# 1-Schematic_ceiling-light.net
KiCad netlist of a schematic drawn in EasyEDA
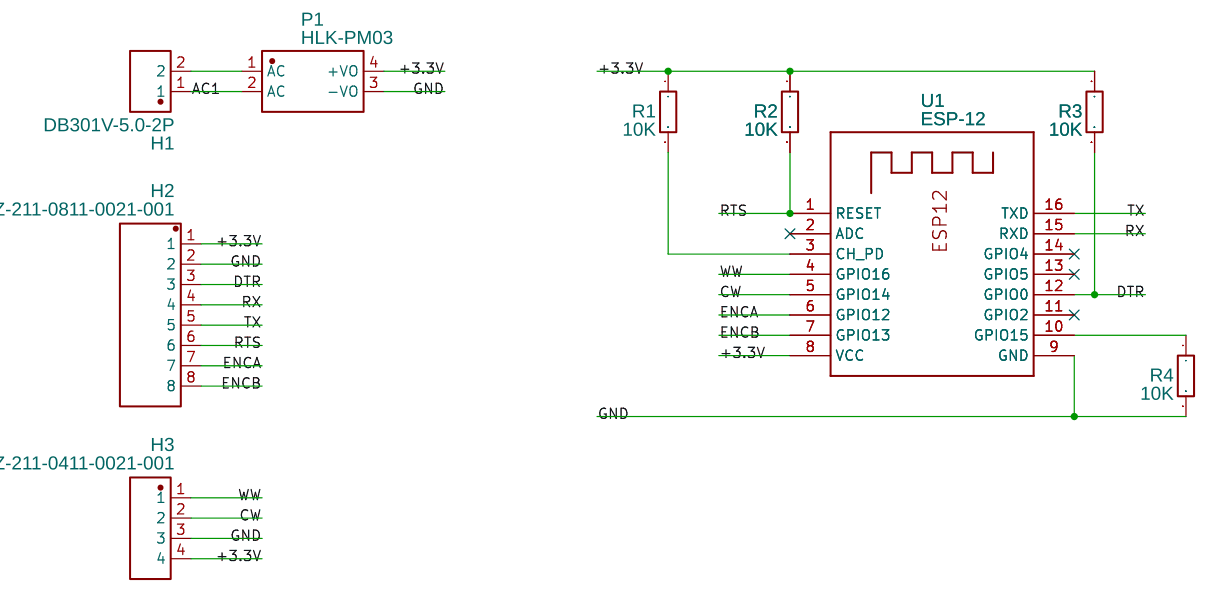
[diagram p0: schematic sheet]

(export (version "E")
  (design (tool "Eeschema 10.0.6"))
  (components
    (comp (ref "H1")
      (value "DB301V-5.0-2P")
      (fields (field (name "BOM_Supplier Part") "C395882"))
      (libsource (lib "") (part "Unknown_100_85"))
    )
    (comp (ref "H2")
      (value "Z-211-0811-0021-001")
      (fields (field (name "BOM_Supplier Part") "C190820"))
      (libsource (lib "") (part "Z-211-0811-0021-001"))
    )
    (comp (ref "H3")
      (value "Z-211-0411-0021-001")
      (fields (field (name "BOM_Supplier Part") "C152150"))
      (libsource (lib "") (part "Z-211-0411-0021-001"))
    )
    (comp (ref "P1")
      (value "HLK-PM03")
      (fields (field (name "BOM_Supplier Part") "C209904"))
      (libsource (lib "") (part "Unknown_185_85"))
    )
    (comp (ref "R1")
      (value "10K")
      (fields
        (field (name "BOM_Manufacturer Part") "RMC16K103FTP")
        (field (name "BOM_Supplier Part") "C323556")
      )
      (libsource (lib "") (part "RMC16K103FTP"))
    )
    (comp (ref "R2")
      (value "10K")
      (fields
        (field (name "BOM_Manufacturer Part") "RMC16K103FTP")
        (field (name "BOM_Supplier Part") "C323556")
      )
      (libsource (lib "") (part "RMC16K103FTP"))
    )
    (comp (ref "R3")
      (value "10K")
      (fields
        (field (name "BOM_Manufacturer Part") "RMC16K103FTP")
        (field (name "BOM_Supplier Part") "C323556")
      )
      (libsource (lib "") (part "RMC16K103FTP"))
    )
    (comp (ref "R4")
      (value "10K")
      (fields
        (field (name "BOM_Manufacturer Part") "RMC16K103FTP")
        (field (name "BOM_Supplier Part") "C323556")
      )
      (libsource (lib "") (part "RMC16K103FTP"))
    )
    (comp (ref "U1") (value "ESP-12") (libsource (lib "") (part "ESP-12")))
  )
  (nets
    (net (code "1") (name "/+3.3V") (class "Default")
      (node (ref "H2") (pin "1") (pinfunction "1_1") (pintype "unspecified"))
      (node (ref "H3") (pin "4") (pinfunction "4_4") (pintype "unspecified"))
      (node (ref "P1") (pin "4") (pinfunction "+VO_4") (pintype "unspecified"))
      (node (ref "R1") (pin "1") (pinfunction "1_1") (pintype "unspecified"))
      (node (ref "R2") (pin "1") (pinfunction "1_1") (pintype "unspecified"))
      (node (ref "R3") (pin "1") (pinfunction "1_1") (pintype "unspecified"))
      (node (ref "U1") (pin "8") (pinfunction "VCC_8") (pintype "passive"))
    )
    (net (code "2") (name "/AC1") (class "Default")
      (node (ref "H1") (pin "1") (pinfunction "1_1") (pintype "unspecified"))
      (node (ref "P1") (pin "2") (pinfunction "AC_2") (pintype "unspecified"))
    )
    (net (code "3") (name "/CW") (class "Default")
      (node (ref "H3") (pin "2") (pinfunction "2_2") (pintype "unspecified"))
      (node (ref "U1") (pin "5") (pinfunction "GPIO14_5") (pintype "unspecified"))
    )
    (net (code "4") (name "/DTR") (class "Default")
      (node (ref "H2") (pin "3") (pinfunction "3_3") (pintype "unspecified"))
      (node (ref "R3") (pin "2") (pinfunction "2_2") (pintype "unspecified"))
      (node (ref "U1") (pin "12") (pinfunction "GPIO0_12") (pintype "unspecified"))
    )
    (net (code "5") (name "/ENCA") (class "Default")
      (node (ref "H2") (pin "7") (pinfunction "7_7") (pintype "unspecified"))
      (node (ref "U1") (pin "6") (pinfunction "GPIO12_6") (pintype "unspecified"))
    )
    (net (code "6") (name "/ENCB") (class "Default")
      (node (ref "H2") (pin "8") (pinfunction "8_8") (pintype "unspecified"))
      (node (ref "U1") (pin "7") (pinfunction "GPIO13_7") (pintype "unspecified"))
    )
    (net (code "7") (name "/GND") (class "Default")
      (node (ref "H2") (pin "2") (pinfunction "2_2") (pintype "unspecified"))
      (node (ref "H3") (pin "3") (pinfunction "3_3") (pintype "unspecified"))
      (node (ref "P1") (pin "3") (pinfunction "-VO_3") (pintype "unspecified"))
      (node (ref "R4") (pin "2") (pinfunction "2_2") (pintype "unspecified"))
      (node (ref "U1") (pin "9") (pinfunction "GND_9") (pintype "passive"))
    )
    (net (code "8") (name "/RTS") (class "Default")
      (node (ref "H2") (pin "6") (pinfunction "6_6") (pintype "unspecified"))
      (node (ref "R2") (pin "2") (pinfunction "2_2") (pintype "unspecified"))
      (node (ref "U1") (pin "1") (pinfunction "RESET_1") (pintype "input"))
    )
    (net (code "9") (name "/RX") (class "Default")
      (node (ref "H2") (pin "4") (pinfunction "4_4") (pintype "unspecified"))
      (node (ref "U1") (pin "15") (pinfunction "RXD_15") (pintype "input"))
    )
    (net (code "10") (name "/TX") (class "Default")
      (node (ref "H2") (pin "5") (pinfunction "5_5") (pintype "unspecified"))
      (node (ref "U1") (pin "16") (pinfunction "TXD_16") (pintype "output"))
    )
    (net (code "11") (name "/WW") (class "Default")
      (node (ref "H3") (pin "1") (pinfunction "1_1") (pintype "unspecified"))
      (node (ref "U1") (pin "4") (pinfunction "GPIO16_4") (pintype "unspecified"))
    )
    (net (code "12") (name "Net-(H1-Pad2)") (class "Default")
      (node (ref "H1") (pin "2") (pinfunction "2_2") (pintype "unspecified"))
      (node (ref "P1") (pin "1") (pinfunction "AC_1") (pintype "unspecified"))
    )
    (net (code "13") (name "Net-(U1-CH_PD)") (class "Default")
      (node (ref "R1") (pin "2") (pinfunction "2_2") (pintype "unspecified"))
      (node (ref "U1") (pin "3") (pinfunction "CH_PD_3") (pintype "input"))
    )
    (net (code "14") (name "Net-(U1-GPIO15)") (class "Default")
      (node (ref "R4") (pin "1") (pinfunction "1_1") (pintype "unspecified"))
      (node (ref "U1") (pin "10") (pinfunction "GPIO15_10") (pintype "unspecified"))
    )
    (net (code "15") (name "unconnected-(U1-ADC-Pad2)") (class "Default")
      (node (ref "U1") (pin "2") (pinfunction "ADC_2") (pintype "unspecified+no_connect"))
    )
    (net (code "16") (name "unconnected-(U1-GPIO2-Pad11)") (class "Default")
      (node (ref "U1") (pin "11") (pinfunction "GPIO2_11") (pintype "unspecified+no_connect"))
    )
    (net (code "17") (name "unconnected-(U1-GPIO4-Pad14)") (class "Default")
      (node (ref "U1") (pin "14") (pinfunction "GPIO4_14") (pintype "unspecified+no_connect"))
    )
    (net (code "18") (name "unconnected-(U1-GPIO5-Pad13)") (class "Default")
      (node (ref "U1") (pin "13") (pinfunction "GPIO5_13") (pintype "unspecified+no_connect"))
    )
  )
)
